# TSOC_GROVEY_ONE_R1_0.net
KiCad netlist of a schematic drawn in EAGLE
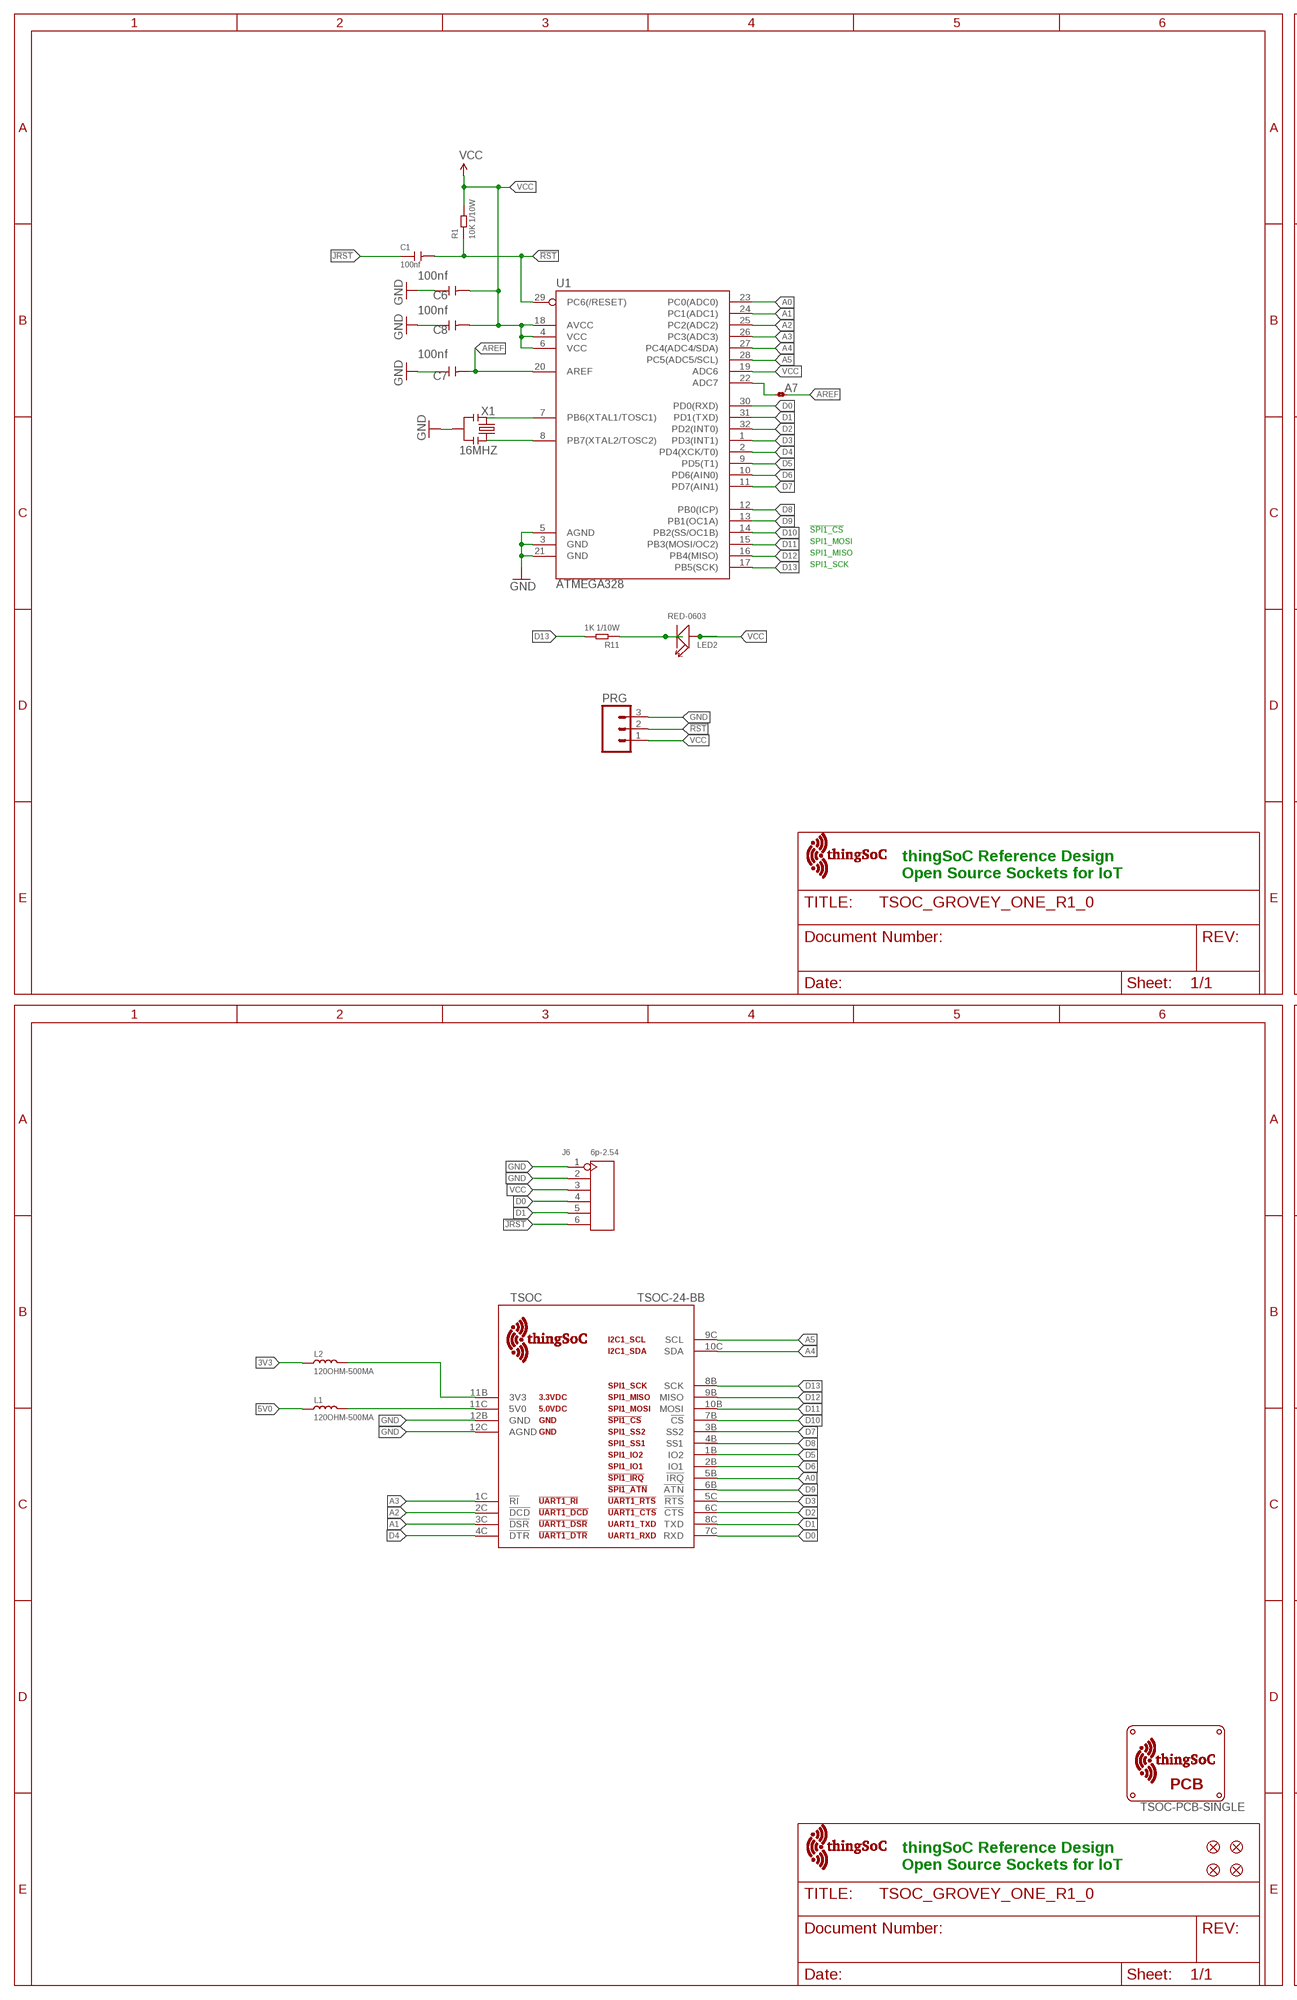
[diagram p0: schematic, sheet 1, part 1 of 2]
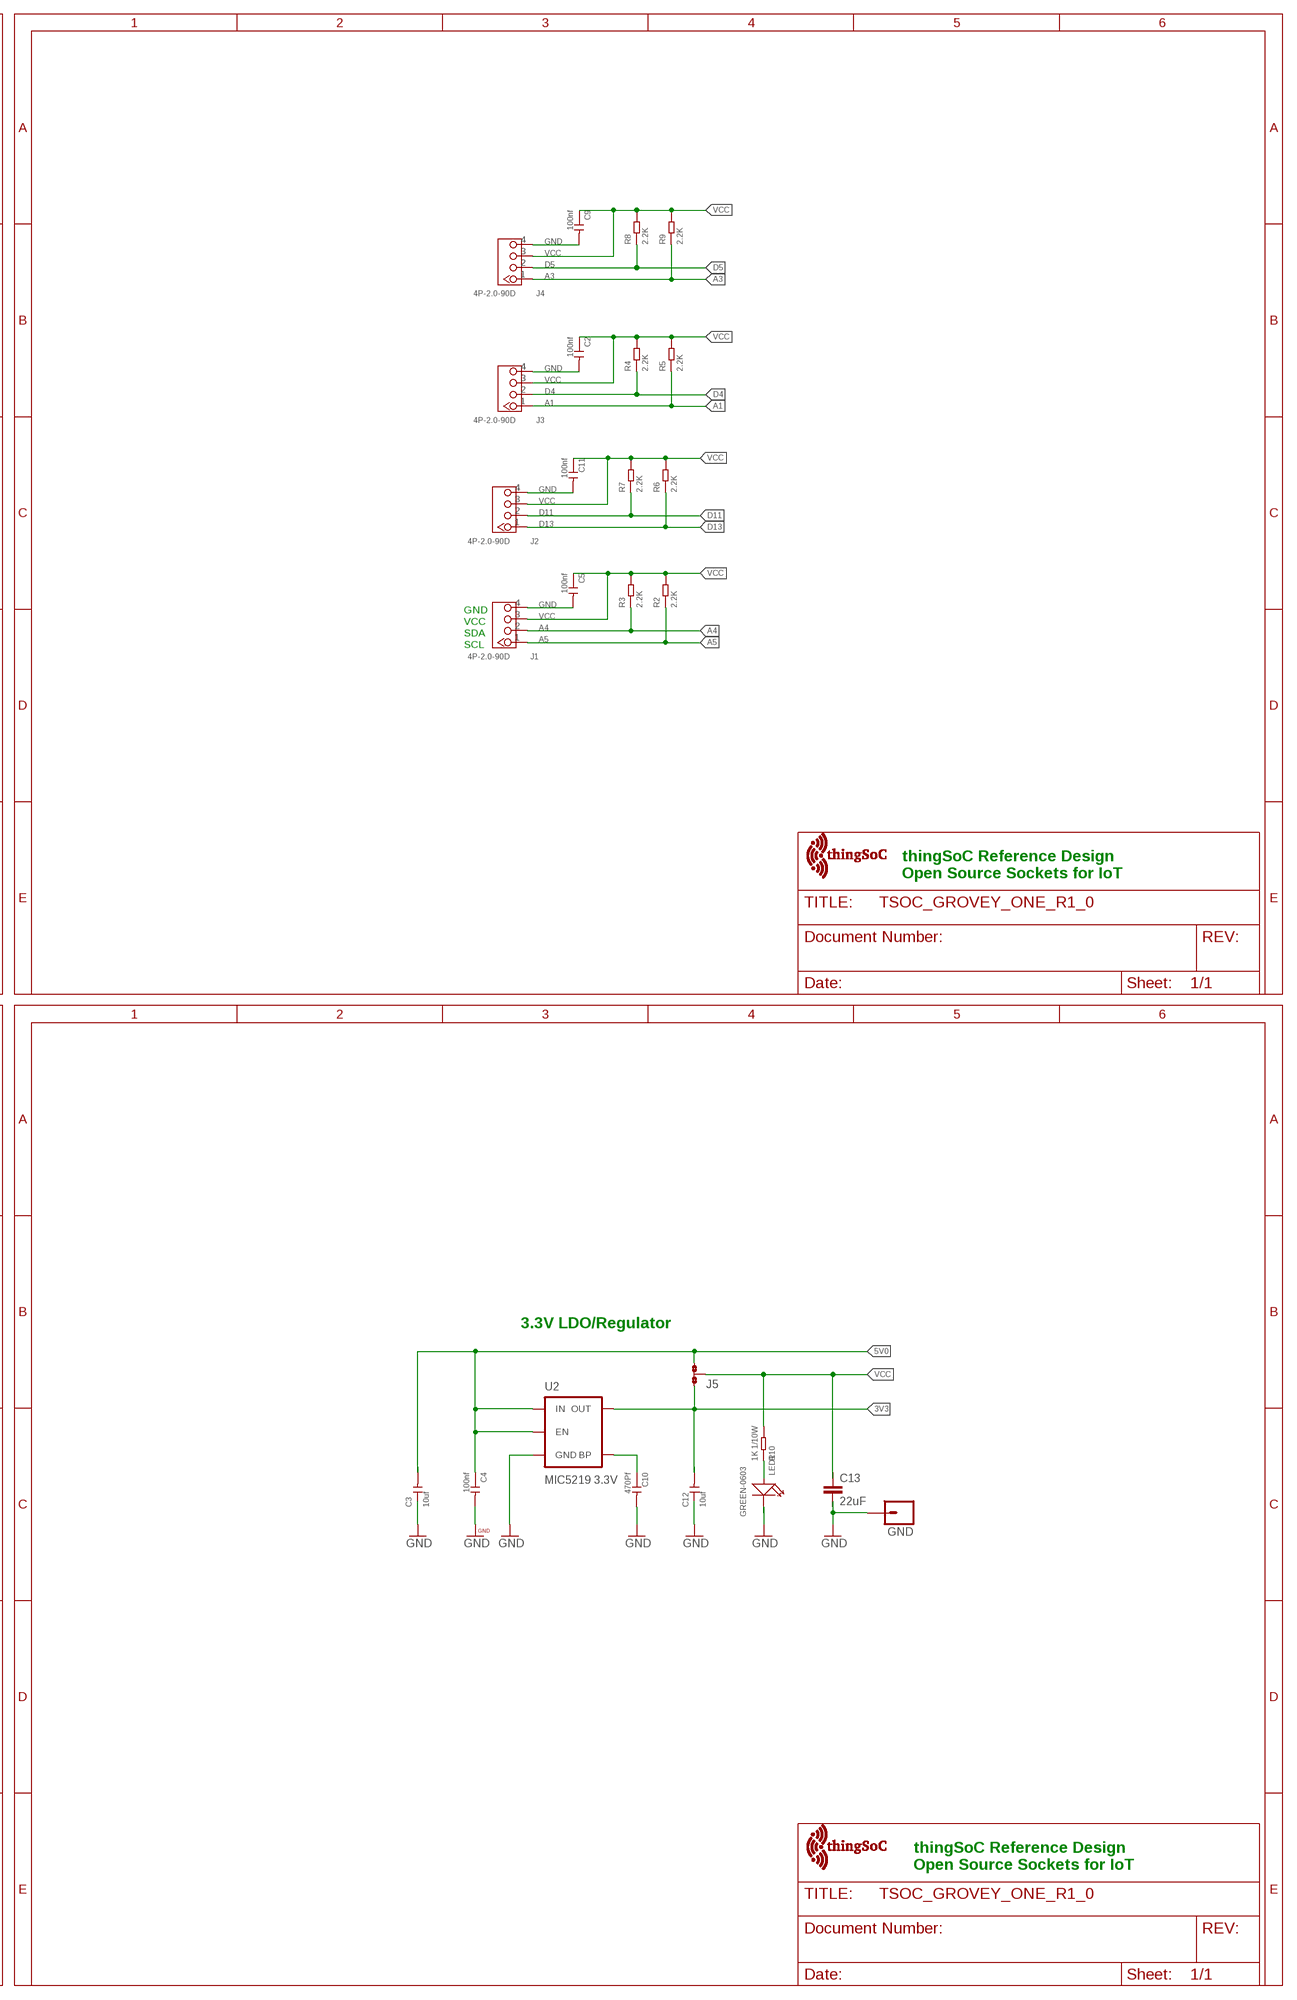
[diagram p1: schematic, sheet 1, part 2 of 2]

(export (version "E")
  (design (tool "Eeschema 10.0.6"))
  (components
    (comp (ref "$$U$2")
      (value "TSOC-PCB-SINGLE")
      (footprint "eagle-import:TSOC-BB-BRD-DIM")
      (libsource (lib "eagle-import") (part "TSOC-PCB-SINGLE"))
    )
    (comp (ref "A7")
      (value "JMP-2-NO")
      (footprint "eagle-import:JMP-2-NO")
      (libsource (lib "eagle-import") (part "JMP-2-NO"))
    )
    (comp (ref "C1")
      (value "100nf")
      (footprint "eagle-import:C0603")
      (fields (field (name "MPN") "CC0603KRX7R9BB104"))
      (libsource (lib "eagle-import") (part "CERAMIC-100NF-50V-10%-X7R(0603)"))
    )
    (comp (ref "C2")
      (value "100nf")
      (footprint "eagle-import:C0603")
      (fields (field (name "MPN") "CC0603KRX7R9BB104"))
      (libsource (lib "eagle-import") (part "CERAMIC-100NF-50V-10%-X7R(0603)"))
    )
    (comp (ref "C3")
      (value "10uf")
      (footprint "eagle-import:C0603")
      (fields (field (name "MPN") "CC0603KRX5R6BB106"))
      (libsource (lib "eagle-import") (part "CERAMIC-10UF-10V-10%-X5R(0603)"))
    )
    (comp (ref "C4")
      (value "100nf")
      (footprint "eagle-import:C0603")
      (fields (field (name "MPN") "CC0603KRX7R9BB104"))
      (libsource (lib "eagle-import") (part "CERAMIC-100NF-50V-10%-X7R(0603)"))
    )
    (comp (ref "C5")
      (value "100nf")
      (footprint "eagle-import:C0603")
      (fields (field (name "MPN") "CC0603KRX7R9BB104"))
      (libsource (lib "eagle-import") (part "CERAMIC-100NF-50V-10%-X7R(0603)"))
    )
    (comp (ref "C6")
      (value "100nf")
      (footprint "eagle-import:C0603")
      (fields (field (name "MPN") "CC0603KRX7R9BB104"))
      (libsource (lib "eagle-import") (part "CERAMIC-100NF-50V-10%-X7R(0603)"))
    )
    (comp (ref "C7")
      (value "100nf")
      (footprint "eagle-import:C0603")
      (fields (field (name "MPN") "CC0603KRX7R9BB104"))
      (libsource (lib "eagle-import") (part "CERAMIC-100NF-50V-10%-X7R(0603)"))
    )
    (comp (ref "C8")
      (value "100nf")
      (footprint "eagle-import:C0603")
      (fields (field (name "MPN") "CC0603KRX7R9BB104"))
      (libsource (lib "eagle-import") (part "CERAMIC-100NF-50V-10%-X7R(0603)"))
    )
    (comp (ref "C9")
      (value "100nf")
      (footprint "eagle-import:C0603")
      (fields (field (name "MPN") "CC0603KRX7R9BB104"))
      (libsource (lib "eagle-import") (part "CERAMIC-100NF-50V-10%-X7R(0603)"))
    )
    (comp (ref "C10")
      (value "470Pf")
      (footprint "eagle-import:C0603")
      (fields (field (name "MPN") "CC0603KRX7R9BB104"))
      (libsource (lib "eagle-import") (part "CERAMIC-100NF-50V-10%-X7R(0603)"))
    )
    (comp (ref "C11")
      (value "100nf")
      (footprint "eagle-import:C0603")
      (fields (field (name "MPN") "CC0603KRX7R9BB104"))
      (libsource (lib "eagle-import") (part "CERAMIC-100NF-50V-10%-X7R(0603)"))
    )
    (comp (ref "C12")
      (value "10uf")
      (footprint "eagle-import:C0603")
      (fields (field (name "MPN") "CC0603KRX5R6BB106"))
      (libsource (lib "eagle-import") (part "CERAMIC-10UF-10V-10%-X5R(0603)"))
    )
    (comp (ref "C13")
      (value "22uF")
      (footprint "eagle-import:EIA-1206")
      (libsource (lib "eagle-import") (part "CAP-1206"))
    )
    (comp (ref "FID1")
      (value "FIDUCIALUFIDUCIAL")
      (footprint "eagle-import:MICRO-FIDUCIAL")
      (libsource (lib "eagle-import") (part "FIDUCIALUFIDUCIAL"))
    )
    (comp (ref "FID2")
      (value "FIDUCIALUFIDUCIAL")
      (footprint "eagle-import:MICRO-FIDUCIAL")
      (libsource (lib "eagle-import") (part "FIDUCIALUFIDUCIAL"))
    )
    (comp (ref "FID3")
      (value "FIDUCIALUFIDUCIAL")
      (footprint "eagle-import:MICRO-FIDUCIAL")
      (libsource (lib "eagle-import") (part "FIDUCIALUFIDUCIAL"))
    )
    (comp (ref "FID4")
      (value "FIDUCIALUFIDUCIAL")
      (footprint "eagle-import:MICRO-FIDUCIAL")
      (libsource (lib "eagle-import") (part "FIDUCIALUFIDUCIAL"))
    )
    (comp (ref "GND")
      (value "M01PTH")
      (footprint "eagle-import:1X01")
      (libsource (lib "eagle-import") (part "M01PTH"))
    )
    (comp (ref "J1")
      (value "4P-2.0-90D")
      (footprint "eagle-import:HW4-2.0-90D")
      (libsource (lib "eagle-import") (part "GROVE-CONNECTOR-DIP-90D(4P-2.0)"))
    )
    (comp (ref "J2")
      (value "4P-2.0-90D")
      (footprint "eagle-import:HW4-2.0-90D")
      (libsource (lib "eagle-import") (part "GROVE-CONNECTOR-DIP-90D(4P-2.0)"))
    )
    (comp (ref "J3")
      (value "4P-2.0-90D")
      (footprint "eagle-import:HW4-2.0-90D")
      (libsource (lib "eagle-import") (part "GROVE-CONNECTOR-DIP-90D(4P-2.0)"))
    )
    (comp (ref "J4")
      (value "4P-2.0-90D")
      (footprint "eagle-import:HW4-2.0-90D")
      (libsource (lib "eagle-import") (part "GROVE-CONNECTOR-DIP-90D(4P-2.0)"))
    )
    (comp (ref "J5")
      (value "NO")
      (footprint "eagle-import:JMP-3-NO-PTH-2.54")
      (libsource (lib "eagle-import") (part "JMP-3-NO-PTH"))
    )
    (comp (ref "J6")
      (value "6p-2.54")
      (footprint "eagle-import:H6-2.54")
      (fields (field (name "MPN") "P125-1106A1BS116A1"))
      (libsource (lib "eagle-import") (part "DIP-BLACK-MALE-HEADER(6P-2.54)"))
    )
    (comp (ref "L1")
      (value "120OHM-500MA")
      (footprint "eagle-import:L0603")
      (fields (field (name "MPN") "BLM18AG121SN1D"))
      (libsource (lib "eagle-import") (part "SMD-FERRITE-CHIP-120-OHM-500MA(0603)"))
    )
    (comp (ref "L2")
      (value "120OHM-500MA")
      (footprint "eagle-import:L0603")
      (fields (field (name "MPN") "BLM18AG121SN1D"))
      (libsource (lib "eagle-import") (part "SMD-FERRITE-CHIP-120-OHM-500MA(0603)"))
    )
    (comp (ref "LED1")
      (value "GREEN-0603")
      (footprint "eagle-import:LED-0603")
      (fields (field (name "MPN") "19-217-G7C-AN1P2-3T"))
      (libsource (lib "eagle-import") (part "SMD-LED-CLEAR-GREEN(0603)"))
    )
    (comp (ref "LED2")
      (value "RED-0603")
      (footprint "eagle-import:LED-0603")
      (fields (field (name "MPN") "19-217-G7C-AN1P2-3T"))
      (libsource (lib "eagle-import") (part "SMD-LED-CLEAR-GREEN(0603)"))
    )
    (comp (ref "PRG")
      (value "M03PTH")
      (footprint "eagle-import:1X03")
      (libsource (lib "eagle-import") (part "M03PTH"))
    )
    (comp (ref "R1")
      (value "10K 1/10W")
      (footprint "eagle-import:R0603")
      (fields (field (name "MPN") "RC0603JR-0710KL"))
      (libsource (lib "eagle-import") (part "SMD-RES-10K-5%-1/10W(0603)"))
    )
    (comp (ref "R2")
      (value "2.2K")
      (footprint "eagle-import:R0603")
      (fields (field (name "MPN") "RC0603JR-072K2L"))
      (libsource (lib "eagle-import") (part "SMD-RES-2.2K-5%-1/10W(0603)"))
    )
    (comp (ref "R3")
      (value "2.2K")
      (footprint "eagle-import:R0603")
      (fields (field (name "MPN") "RC0603JR-072K2L"))
      (libsource (lib "eagle-import") (part "SMD-RES-2.2K-5%-1/10W(0603)"))
    )
    (comp (ref "R4")
      (value "2.2K")
      (footprint "eagle-import:R0603")
      (fields (field (name "MPN") "RC0603JR-072K2L"))
      (libsource (lib "eagle-import") (part "SMD-RES-2.2K-5%-1/10W(0603)"))
    )
    (comp (ref "R5")
      (value "2.2K")
      (footprint "eagle-import:R0603")
      (fields (field (name "MPN") "RC0603JR-072K2L"))
      (libsource (lib "eagle-import") (part "SMD-RES-2.2K-5%-1/10W(0603)"))
    )
    (comp (ref "R6")
      (value "2.2K")
      (footprint "eagle-import:R0603")
      (fields (field (name "MPN") "RC0603JR-072K2L"))
      (libsource (lib "eagle-import") (part "SMD-RES-2.2K-5%-1/10W(0603)"))
    )
    (comp (ref "R7")
      (value "2.2K")
      (footprint "eagle-import:R0603")
      (fields (field (name "MPN") "RC0603JR-072K2L"))
      (libsource (lib "eagle-import") (part "SMD-RES-2.2K-5%-1/10W(0603)"))
    )
    (comp (ref "R8")
      (value "2.2K")
      (footprint "eagle-import:R0603")
      (fields (field (name "MPN") "RC0603JR-072K2L"))
      (libsource (lib "eagle-import") (part "SMD-RES-2.2K-5%-1/10W(0603)"))
    )
    (comp (ref "R9")
      (value "2.2K")
      (footprint "eagle-import:R0603")
      (fields (field (name "MPN") "RC0603JR-072K2L"))
      (libsource (lib "eagle-import") (part "SMD-RES-2.2K-5%-1/10W(0603)"))
    )
    (comp (ref "R10")
      (value "1K 1/10W")
      (footprint "eagle-import:R0603")
      (fields (field (name "MPN") "RC0603JR-071KL"))
      (libsource (lib "eagle-import") (part "SMD-RES-1K-5%-1/10W(0603)"))
    )
    (comp (ref "R11")
      (value "1K 1/10W")
      (footprint "eagle-import:R0603")
      (fields (field (name "MPN") "RC0603JR-071KL"))
      (libsource (lib "eagle-import") (part "SMD-RES-1K-5%-1/10W(0603)"))
    )
    (comp (ref "TSOC")
      (value "TSOC-24-BB")
      (footprint "eagle-import:TSOC-BB-S24")
      (libsource (lib "eagle-import") (part "TSOC-24-BB"))
    )
    (comp (ref "U$3")
      (value "TSOC-LOGO-SMALL")
      (footprint "eagle-import:TSOC-LOGO-SML")
      (libsource (lib "eagle-import") (part "TSOC-LOGO-SMALL"))
    )
    (comp (ref "U$100")
      (value "TSOC-LOGO-SMALL")
      (footprint "eagle-import:TSOC-LOGO-SML")
      (libsource (lib "eagle-import") (part "TSOC-LOGO-SMALL"))
    )
    (comp (ref "U$101")
      (value "TSOC-LOGO-LRG")
      (footprint "eagle-import:TSOC-LOGO-LRG")
      (libsource (lib "eagle-import") (part "TSOC-LOGO-LRG"))
    )
    (comp (ref "U$103")
      (value "TSOC-LOGO-SMALL")
      (footprint "eagle-import:TSOC-LOGO-SML")
      (libsource (lib "eagle-import") (part "TSOC-LOGO-SMALL"))
    )
    (comp (ref "U1")
      (value "ATMEGA328")
      (footprint "eagle-import:TQFP32-08")
      (libsource (lib "eagle-import") (part "ATMEGA168"))
    )
    (comp (ref "U2")
      (value "MIC5219 3.3V")
      (footprint "eagle-import:SOT23-5")
      (libsource (lib "eagle-import") (part "V_REG_MIC52193.3V"))
    )
    (comp (ref "X1")
      (value "16MHZ")
      (footprint "eagle-import:X3-SMD-3.6X1.3X0.8MM")
      (fields (field (name "MPN") "CSTCE16M0V53-R0"))
      (libsource (lib "eagle-import") (part "SMD-RESONATOR-16MHZ-15PF-0.5%-40R(3P-3.2X1.3MM)"))
    )
  )
  (nets
    (net (code "1") (name "/~{JRST}") (class "Default")
      (node (ref "C1") (pin "1") (pinfunction "1_1") (pintype "passive"))
      (node (ref "J6") (pin "6") (pinfunction "6_6") (pintype "bidirectional"))
    )
    (net (code "2") (name "/~{RST}") (class "Default")
      (node (ref "C1") (pin "2") (pinfunction "2_2") (pintype "passive"))
      (node (ref "PRG") (pin "2") (pinfunction "2_2") (pintype "passive"))
      (node (ref "R1") (pin "1") (pinfunction "1_1") (pintype "passive"))
      (node (ref "U1") (pin "29") (pinfunction "PC6(/RESET)_29") (pintype "bidirectional"))
    )
    (net (code "3") (name "3V3") (class "Default")
      (node (ref "C12") (pin "2") (pinfunction "2_2") (pintype "passive"))
      (node (ref "J5") (pin "1") (pinfunction "1_1") (pintype "passive"))
      (node (ref "L2") (pin "1") (pinfunction "1_1") (pintype "passive"))
      (node (ref "U2") (pin "5") (pinfunction "OUT_5") (pintype "passive"))
    )
    (net (code "4") (name "5V0") (class "Default")
      (node (ref "C3") (pin "2") (pinfunction "2_2") (pintype "passive"))
      (node (ref "C4") (pin "1") (pinfunction "1_1") (pintype "passive"))
      (node (ref "J5") (pin "3") (pinfunction "3_3") (pintype "passive"))
      (node (ref "L1") (pin "1") (pinfunction "1_1") (pintype "passive"))
      (node (ref "U2") (pin "1") (pinfunction "IN_1") (pintype "input"))
      (node (ref "U2") (pin "3") (pinfunction "EN_3") (pintype "input"))
    )
    (net (code "5") (name "A0") (class "Default")
      (node (ref "TSOC") (pin "5B") (pinfunction "~{IRQ}_5B") (pintype "bidirectional"))
      (node (ref "U1") (pin "23") (pinfunction "PC0(ADC0)_23") (pintype "bidirectional"))
    )
    (net (code "6") (name "A1") (class "Default")
      (node (ref "J3") (pin "1") (pinfunction "1_1") (pintype "bidirectional"))
      (node (ref "R5") (pin "1") (pinfunction "1_1") (pintype "passive"))
      (node (ref "TSOC") (pin "3C") (pinfunction "~{DSR}_3C") (pintype "bidirectional"))
      (node (ref "U1") (pin "24") (pinfunction "PC1(ADC1)_24") (pintype "bidirectional"))
    )
    (net (code "7") (name "A2") (class "Default")
      (node (ref "TSOC") (pin "2C") (pinfunction "~{DCD}_2C") (pintype "bidirectional"))
      (node (ref "U1") (pin "25") (pinfunction "PC2(ADC2)_25") (pintype "bidirectional"))
    )
    (net (code "8") (name "A3") (class "Default")
      (node (ref "J4") (pin "1") (pinfunction "1_1") (pintype "bidirectional"))
      (node (ref "R9") (pin "1") (pinfunction "1_1") (pintype "passive"))
      (node (ref "TSOC") (pin "1C") (pinfunction "~{RI}_1C") (pintype "bidirectional"))
      (node (ref "U1") (pin "26") (pinfunction "PC3(ADC3)_26") (pintype "bidirectional"))
    )
    (net (code "9") (name "A4") (class "Default")
      (node (ref "J1") (pin "2") (pinfunction "2_2") (pintype "bidirectional"))
      (node (ref "R3") (pin "1") (pinfunction "1_1") (pintype "passive"))
      (node (ref "TSOC") (pin "10C") (pinfunction "SDA_10C") (pintype "bidirectional"))
      (node (ref "U1") (pin "27") (pinfunction "PC4(ADC4/SDA)_27") (pintype "bidirectional"))
    )
    (net (code "10") (name "A5") (class "Default")
      (node (ref "J1") (pin "1") (pinfunction "1_1") (pintype "bidirectional"))
      (node (ref "R2") (pin "1") (pinfunction "1_1") (pintype "passive"))
      (node (ref "TSOC") (pin "9C") (pinfunction "SCL_9C") (pintype "bidirectional"))
      (node (ref "U1") (pin "28") (pinfunction "PC5(ADC5/SCL)_28") (pintype "bidirectional"))
    )
    (net (code "11") (name "AREF") (class "Default")
      (node (ref "A7") (pin "2") (pinfunction "2_2") (pintype "passive"))
      (node (ref "C7") (pin "2") (pinfunction "2_2") (pintype "passive"))
      (node (ref "U1") (pin "20") (pinfunction "AREF_20") (pintype "bidirectional"))
    )
    (net (code "12") (name "D0") (class "Default")
      (node (ref "J6") (pin "4") (pinfunction "4_4") (pintype "bidirectional"))
      (node (ref "TSOC") (pin "7C") (pinfunction "RXD_7C") (pintype "bidirectional"))
      (node (ref "U1") (pin "30") (pinfunction "PD0(RXD)_30") (pintype "bidirectional"))
    )
    (net (code "13") (name "D1") (class "Default")
      (node (ref "J6") (pin "5") (pinfunction "5_5") (pintype "bidirectional"))
      (node (ref "TSOC") (pin "8C") (pinfunction "TXD_8C") (pintype "bidirectional"))
      (node (ref "U1") (pin "31") (pinfunction "PD1(TXD)_31") (pintype "bidirectional"))
    )
    (net (code "14") (name "D2") (class "Default")
      (node (ref "TSOC") (pin "6C") (pinfunction "~{CTS}_6C") (pintype "bidirectional"))
      (node (ref "U1") (pin "32") (pinfunction "PD2(INT0)_32") (pintype "bidirectional"))
    )
    (net (code "15") (name "D3") (class "Default")
      (node (ref "TSOC") (pin "5C") (pinfunction "~{RTS}_5C") (pintype "bidirectional"))
      (node (ref "U1") (pin "1") (pinfunction "PD3(INT1)_1") (pintype "bidirectional"))
    )
    (net (code "16") (name "D4") (class "Default")
      (node (ref "J3") (pin "2") (pinfunction "2_2") (pintype "bidirectional"))
      (node (ref "R4") (pin "1") (pinfunction "1_1") (pintype "passive"))
      (node (ref "TSOC") (pin "4C") (pinfunction "~{DTR}_4C") (pintype "bidirectional"))
      (node (ref "U1") (pin "2") (pinfunction "PD4(XCK/T0)_2") (pintype "bidirectional"))
    )
    (net (code "17") (name "D5") (class "Default")
      (node (ref "J4") (pin "2") (pinfunction "2_2") (pintype "bidirectional"))
      (node (ref "R8") (pin "1") (pinfunction "1_1") (pintype "passive"))
      (node (ref "TSOC") (pin "1B") (pinfunction "IO2_1B") (pintype "bidirectional"))
      (node (ref "U1") (pin "9") (pinfunction "PD5(T1)_9") (pintype "bidirectional"))
    )
    (net (code "18") (name "D6") (class "Default")
      (node (ref "TSOC") (pin "2B") (pinfunction "IO1_2B") (pintype "bidirectional"))
      (node (ref "U1") (pin "10") (pinfunction "PD6(AIN0)_10") (pintype "bidirectional"))
    )
    (net (code "19") (name "D7") (class "Default")
      (node (ref "TSOC") (pin "3B") (pinfunction "SS2_3B") (pintype "bidirectional"))
      (node (ref "U1") (pin "11") (pinfunction "PD7(AIN1)_11") (pintype "bidirectional"))
    )
    (net (code "20") (name "D8") (class "Default")
      (node (ref "TSOC") (pin "4B") (pinfunction "SS1_4B") (pintype "bidirectional"))
      (node (ref "U1") (pin "12") (pinfunction "PB0(ICP)_12") (pintype "bidirectional"))
    )
    (net (code "21") (name "D9") (class "Default")
      (node (ref "TSOC") (pin "6B") (pinfunction "~{ATN}_6B") (pintype "bidirectional"))
      (node (ref "U1") (pin "13") (pinfunction "PB1(OC1A)_13") (pintype "bidirectional"))
    )
    (net (code "22") (name "D10") (class "Default")
      (node (ref "TSOC") (pin "7B") (pinfunction "~{CS}_7B") (pintype "bidirectional"))
      (node (ref "U1") (pin "14") (pinfunction "PB2(SS/OC1B)_14") (pintype "bidirectional"))
    )
    (net (code "23") (name "D11") (class "Default")
      (node (ref "J2") (pin "2") (pinfunction "2_2") (pintype "bidirectional"))
      (node (ref "R7") (pin "1") (pinfunction "1_1") (pintype "passive"))
      (node (ref "TSOC") (pin "10B") (pinfunction "MOSI_10B") (pintype "bidirectional"))
      (node (ref "U1") (pin "15") (pinfunction "PB3(MOSI/OC2)_15") (pintype "bidirectional"))
    )
    (net (code "24") (name "D12") (class "Default")
      (node (ref "TSOC") (pin "9B") (pinfunction "MISO_9B") (pintype "bidirectional"))
      (node (ref "U1") (pin "16") (pinfunction "PB4(MISO)_16") (pintype "bidirectional"))
    )
    (net (code "25") (name "D13") (class "Default")
      (node (ref "J2") (pin "1") (pinfunction "1_1") (pintype "bidirectional"))
      (node (ref "R11") (pin "2") (pinfunction "2_2") (pintype "passive"))
      (node (ref "R6") (pin "1") (pinfunction "1_1") (pintype "passive"))
      (node (ref "TSOC") (pin "8B") (pinfunction "SCK_8B") (pintype "bidirectional"))
      (node (ref "U1") (pin "17") (pinfunction "PB5(SCK)_17") (pintype "bidirectional"))
    )
    (net (code "26") (name "GND") (class "Default")
      (node (ref "C10") (pin "2") (pinfunction "2_2") (pintype "passive"))
      (node (ref "C11") (pin "2") (pinfunction "2_2") (pintype "passive"))
      (node (ref "C12") (pin "1") (pinfunction "1_1") (pintype "passive"))
      (node (ref "C13") (pin "2") (pinfunction "2_2") (pintype "passive"))
      (node (ref "C2") (pin "2") (pinfunction "2_2") (pintype "passive"))
      (node (ref "C3") (pin "1") (pinfunction "1_1") (pintype "passive"))
      (node (ref "C4") (pin "2") (pinfunction "2_2") (pintype "passive"))
      (node (ref "C5") (pin "2") (pinfunction "2_2") (pintype "passive"))
      (node (ref "C6") (pin "1") (pinfunction "1_1") (pintype "passive"))
      (node (ref "C7") (pin "1") (pinfunction "1_1") (pintype "passive"))
      (node (ref "C8") (pin "1") (pinfunction "1_1") (pintype "passive"))
      (node (ref "C9") (pin "2") (pinfunction "2_2") (pintype "passive"))
      (node (ref "GND") (pin "1") (pinfunction "1_1") (pintype "passive"))
      (node (ref "J1") (pin "4") (pinfunction "4_4") (pintype "bidirectional"))
      (node (ref "J2") (pin "4") (pinfunction "4_4") (pintype "bidirectional"))
      (node (ref "J3") (pin "4") (pinfunction "4_4") (pintype "bidirectional"))
      (node (ref "J4") (pin "4") (pinfunction "4_4") (pintype "bidirectional"))
      (node (ref "J6") (pin "1") (pinfunction "1_1") (pintype "bidirectional"))
      (node (ref "J6") (pin "2") (pinfunction "2_2") (pintype "bidirectional"))
      (node (ref "LED1") (pin "-") (pinfunction "-_-") (pintype "passive"))
      (node (ref "PRG") (pin "3") (pinfunction "3_3") (pintype "passive"))
      (node (ref "TSOC") (pin "12B") (pinfunction "GND_12B") (pintype "bidirectional"))
      (node (ref "TSOC") (pin "12C") (pinfunction "AGND_12C") (pintype "bidirectional"))
      (node (ref "U1") (pin "21") (pinfunction "GND_21") (pintype "bidirectional"))
      (node (ref "U1") (pin "3") (pinfunction "GND_3") (pintype "bidirectional"))
      (node (ref "U1") (pin "5") (pinfunction "AGND_5") (pintype "bidirectional"))
      (node (ref "U2") (pin "2") (pinfunction "GND_2") (pintype "input"))
      (node (ref "X1") (pin "2") (pinfunction "2_2") (pintype "passive"))
    )
    (net (code "27") (name "Net-(LED1-Pad+)") (class "Default")
      (node (ref "LED1") (pin "+") (pinfunction "+_+") (pintype "passive"))
      (node (ref "R10") (pin "1") (pinfunction "1_1") (pintype "passive"))
    )
    (net (code "28") (name "Net-(LED2-Pad-)") (class "Default")
      (node (ref "LED2") (pin "-") (pinfunction "-_-") (pintype "passive"))
      (node (ref "R11") (pin "1") (pinfunction "1_1") (pintype "passive"))
    )
    (net (code "29") (name "Net-(TSOC-3V3)") (class "Default")
      (node (ref "L2") (pin "2") (pinfunction "2_2") (pintype "passive"))
      (node (ref "TSOC") (pin "11B") (pinfunction "3V3_11B") (pintype "bidirectional"))
    )
    (net (code "30") (name "Net-(TSOC-5V0)") (class "Default")
      (node (ref "L1") (pin "2") (pinfunction "2_2") (pintype "passive"))
      (node (ref "TSOC") (pin "11C") (pinfunction "5V0_11C") (pintype "bidirectional"))
    )
    (net (code "31") (name "Net-(U1-ADC7)") (class "Default")
      (node (ref "A7") (pin "1") (pinfunction "1_1") (pintype "passive"))
      (node (ref "U1") (pin "22") (pinfunction "ADC7_22") (pintype "bidirectional"))
    )
    (net (code "32") (name "Net-(U1-PB6(XTAL1{slash}TOSC1))") (class "Default")
      (node (ref "U1") (pin "7") (pinfunction "PB6(XTAL1/TOSC1)_7") (pintype "bidirectional"))
      (node (ref "X1") (pin "3") (pinfunction "3_3") (pintype "passive"))
    )
    (net (code "33") (name "Net-(U1-PB7(XTAL2{slash}TOSC2))") (class "Default")
      (node (ref "U1") (pin "8") (pinfunction "PB7(XTAL2/TOSC2)_8") (pintype "bidirectional"))
      (node (ref "X1") (pin "1") (pinfunction "1_1") (pintype "passive"))
    )
    (net (code "34") (name "Net-(U2-BP)") (class "Default")
      (node (ref "C10") (pin "1") (pinfunction "1_1") (pintype "passive"))
      (node (ref "U2") (pin "4") (pinfunction "BP_4") (pintype "input"))
    )
    (net (code "35") (name "VCC") (class "Default")
      (node (ref "C11") (pin "1") (pinfunction "1_1") (pintype "passive"))
      (node (ref "C13") (pin "1") (pinfunction "1_1") (pintype "passive"))
      (node (ref "C2") (pin "1") (pinfunction "1_1") (pintype "passive"))
      (node (ref "C5") (pin "1") (pinfunction "1_1") (pintype "passive"))
      (node (ref "C6") (pin "2") (pinfunction "2_2") (pintype "passive"))
      (node (ref "C8") (pin "2") (pinfunction "2_2") (pintype "passive"))
      (node (ref "C9") (pin "1") (pinfunction "1_1") (pintype "passive"))
      (node (ref "J1") (pin "3") (pinfunction "3_3") (pintype "bidirectional"))
      (node (ref "J2") (pin "3") (pinfunction "3_3") (pintype "bidirectional"))
      (node (ref "J3") (pin "3") (pinfunction "3_3") (pintype "bidirectional"))
      (node (ref "J4") (pin "3") (pinfunction "3_3") (pintype "bidirectional"))
      (node (ref "J5") (pin "2") (pinfunction "2_2") (pintype "passive"))
      (node (ref "J6") (pin "3") (pinfunction "3_3") (pintype "bidirectional"))
      (node (ref "LED2") (pin "+") (pinfunction "+_+") (pintype "passive"))
      (node (ref "PRG") (pin "1") (pinfunction "1_1") (pintype "passive"))
      (node (ref "R1") (pin "2") (pinfunction "2_2") (pintype "passive"))
      (node (ref "R10") (pin "2") (pinfunction "2_2") (pintype "passive"))
      (node (ref "R2") (pin "2") (pinfunction "2_2") (pintype "passive"))
      (node (ref "R3") (pin "2") (pinfunction "2_2") (pintype "passive"))
      (node (ref "R4") (pin "2") (pinfunction "2_2") (pintype "passive"))
      (node (ref "R5") (pin "2") (pinfunction "2_2") (pintype "passive"))
      (node (ref "R6") (pin "2") (pinfunction "2_2") (pintype "passive"))
      (node (ref "R7") (pin "2") (pinfunction "2_2") (pintype "passive"))
      (node (ref "R8") (pin "2") (pinfunction "2_2") (pintype "passive"))
      (node (ref "R9") (pin "2") (pinfunction "2_2") (pintype "passive"))
      (node (ref "U1") (pin "18") (pinfunction "AVCC_18") (pintype "bidirectional"))
      (node (ref "U1") (pin "19") (pinfunction "ADC6_19") (pintype "bidirectional"))
      (node (ref "U1") (pin "4") (pinfunction "VCC_4") (pintype "bidirectional"))
      (node (ref "U1") (pin "6") (pinfunction "VCC_6") (pintype "bidirectional"))
    )
  )
)
